# Stub_Tester.net
KiCad netlist of a schematic drawn in Altium Designer
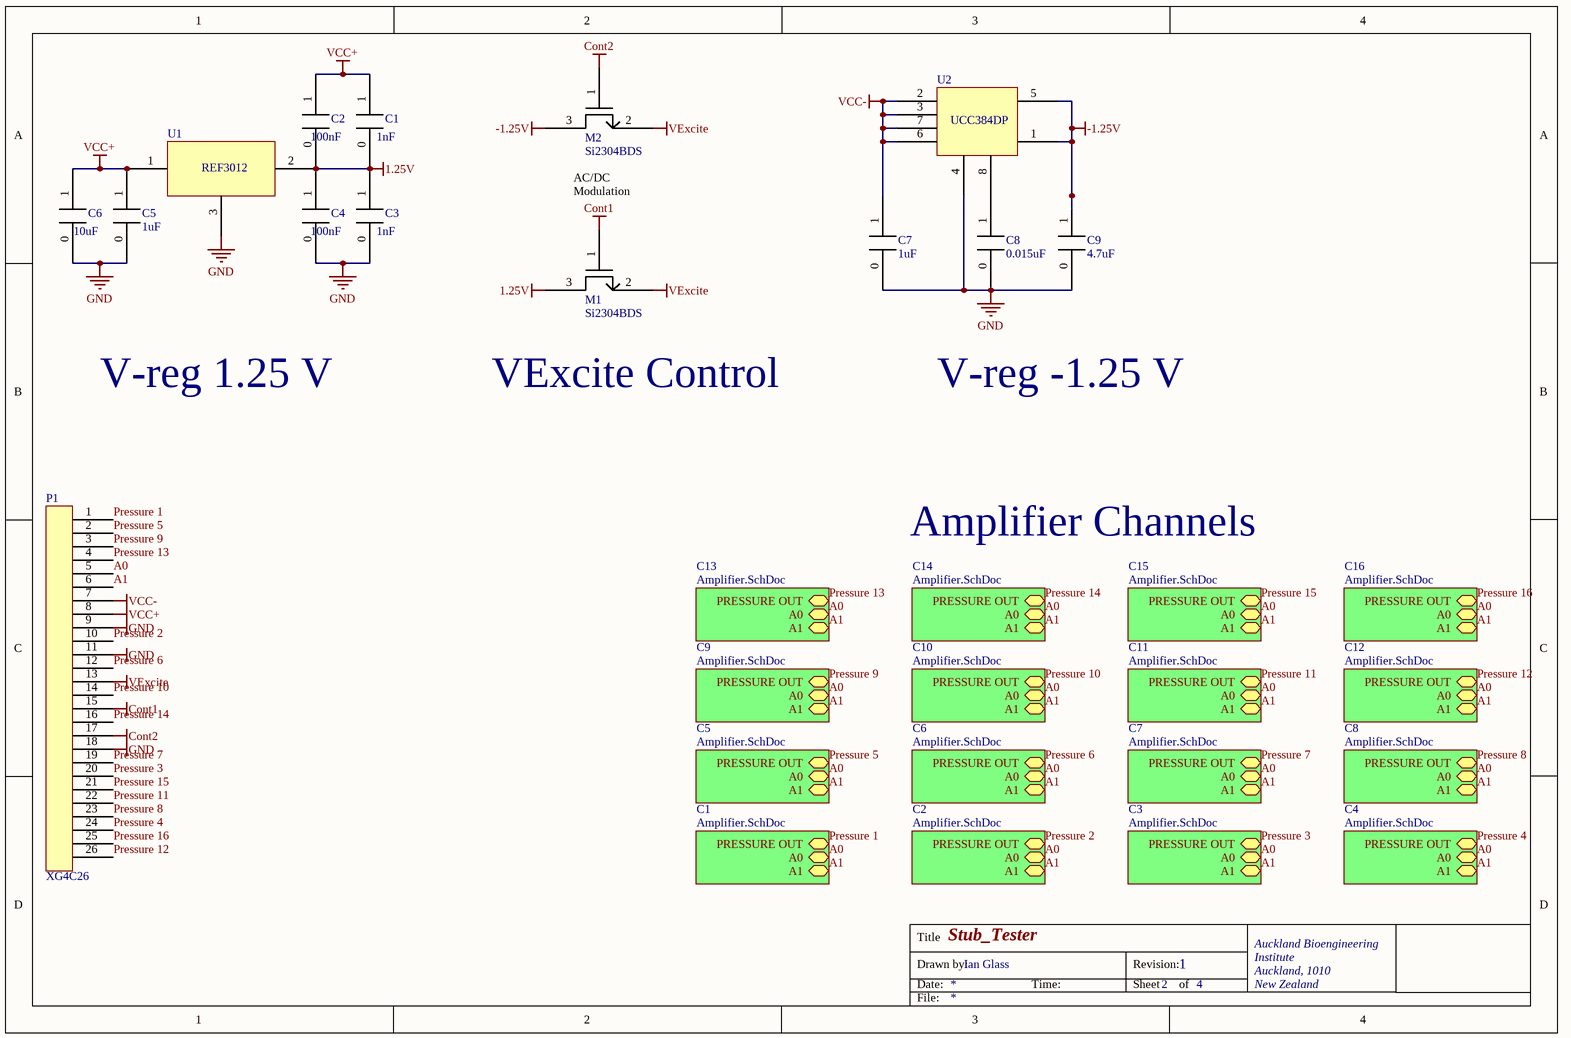
[diagram p0: Stub_Tester.SchDoc]

(export (version "E")
  (design (tool "Eeschema 10.0.6"))
  (components
    (comp (ref "C1")
      (value "1nF")
      (footprint "PcbLib1:C0603 1uF")
      (libsource (lib "Schlib1") (part "C0603 1uF"))
    )
    (comp (ref "C2")
      (value "100nF")
      (footprint "PcbLib1:C0603 1uF")
      (libsource (lib "Schlib1") (part "C0603 1uF"))
    )
    (comp (ref "C3")
      (value "1nF")
      (footprint "PcbLib1:C0603 1uF")
      (libsource (lib "Schlib1") (part "C0603 1uF"))
    )
    (comp (ref "C4")
      (value "100nF")
      (footprint "PcbLib1:C0603 1uF")
      (libsource (lib "Schlib1") (part "C0603 1uF"))
    )
    (comp (ref "C5")
      (value "1uF")
      (footprint "PcbLib1:C0603 1uF")
      (libsource (lib "Schlib1") (part "C0603 1uF"))
    )
    (comp (ref "C6")
      (value "10uF")
      (footprint "PcbLib1:C0603 1uF")
      (libsource (lib "Schlib1") (part "C0603 1uF"))
    )
    (comp (ref "C7")
      (value "1uF")
      (footprint "PcbLib1:C0603 1uF")
      (libsource (lib "Schlib1") (part "C0603 1uF"))
    )
    (comp (ref "C8")
      (value "0.015uF")
      (footprint "PcbLib1:C0603 1uF")
      (libsource (lib "Schlib1") (part "C0603 1uF"))
    )
    (comp (ref "C9")
      (value "4.7uF")
      (footprint "PcbLib1:C0603 1uF")
      (libsource (lib "Schlib1") (part "C0603 1uF"))
    )
    (comp (ref "M1")
      (value "Si2304BDS")
      (footprint "PcbLib1:Si2304BDS")
      (libsource (lib "Schlib1") (part "Si2304BDS"))
    )
    (comp (ref "M2")
      (value "Si2304BDS")
      (footprint "PcbLib1:Si2304BDS")
      (libsource (lib "Schlib1") (part "Si2304BDS"))
    )
    (comp (ref "P1")
      (value "XG4C26")
      (footprint "PcbLib1:XG4C26")
      (libsource (lib "Schlib1") (part "XG4C26"))
    )
    (comp (ref "U1")
      (value "REF3012")
      (footprint "PcbLib1:REF3012")
      (libsource (lib "Schlib1") (part "REF3012"))
    )
    (comp (ref "U2")
      (value "UCC384DP")
      (footprint "PcbLib1:UCC384DP")
      (libsource (lib "Schlib1") (part "UCC384DP"))
    )
  )
  (nets
    (net (code "1") (name "-1.25V") (class "Default")
      (node (ref "C9") (pin "1") (pinfunction "1_1") (pintype "passive"))
      (node (ref "M2") (pin "3") (pinfunction "3_3") (pintype "passive"))
      (node (ref "U2") (pin "1") (pinfunction "1_1") (pintype "passive"))
      (node (ref "U2") (pin "5") (pinfunction "5_5") (pintype "passive"))
    )
    (net (code "2") (name "/A0") (class "Default")
      (node (ref "P1") (pin "5") (pinfunction "5_5") (pintype "passive"))
    )
    (net (code "3") (name "/A1") (class "Default")
      (node (ref "P1") (pin "6") (pinfunction "6_6") (pintype "passive"))
    )
    (net (code "4") (name "/Pressure 1") (class "Default")
      (node (ref "P1") (pin "1") (pinfunction "1_1") (pintype "passive"))
    )
    (net (code "5") (name "/Pressure 2") (class "Default")
      (node (ref "P1") (pin "10") (pinfunction "10_10") (pintype "passive"))
    )
    (net (code "6") (name "/Pressure 3") (class "Default")
      (node (ref "P1") (pin "20") (pinfunction "20_20") (pintype "passive"))
    )
    (net (code "7") (name "/Pressure 4") (class "Default")
      (node (ref "P1") (pin "24") (pinfunction "24_24") (pintype "passive"))
    )
    (net (code "8") (name "/Pressure 5") (class "Default")
      (node (ref "P1") (pin "2") (pinfunction "2_2") (pintype "passive"))
    )
    (net (code "9") (name "/Pressure 6") (class "Default")
      (node (ref "P1") (pin "12") (pinfunction "12_12") (pintype "passive"))
    )
    (net (code "10") (name "/Pressure 7") (class "Default")
      (node (ref "P1") (pin "19") (pinfunction "19_19") (pintype "passive"))
    )
    (net (code "11") (name "/Pressure 8") (class "Default")
      (node (ref "P1") (pin "23") (pinfunction "23_23") (pintype "passive"))
    )
    (net (code "12") (name "/Pressure 9") (class "Default")
      (node (ref "P1") (pin "3") (pinfunction "3_3") (pintype "passive"))
    )
    (net (code "13") (name "/Pressure 10") (class "Default")
      (node (ref "P1") (pin "14") (pinfunction "14_14") (pintype "passive"))
    )
    (net (code "14") (name "/Pressure 11") (class "Default")
      (node (ref "P1") (pin "22") (pinfunction "22_22") (pintype "passive"))
    )
    (net (code "15") (name "/Pressure 12") (class "Default")
      (node (ref "P1") (pin "26") (pinfunction "26_26") (pintype "passive"))
    )
    (net (code "16") (name "/Pressure 13") (class "Default")
      (node (ref "P1") (pin "4") (pinfunction "4_4") (pintype "passive"))
    )
    (net (code "17") (name "/Pressure 14") (class "Default")
      (node (ref "P1") (pin "16") (pinfunction "16_16") (pintype "passive"))
    )
    (net (code "18") (name "/Pressure 15") (class "Default")
      (node (ref "P1") (pin "21") (pinfunction "21_21") (pintype "passive"))
    )
    (net (code "19") (name "/Pressure 16") (class "Default")
      (node (ref "P1") (pin "25") (pinfunction "25_25") (pintype "passive"))
    )
    (net (code "20") (name "1.25V") (class "Default")
      (node (ref "C1") (pin "0") (pinfunction "0_0") (pintype "passive"))
      (node (ref "C2") (pin "0") (pinfunction "0_0") (pintype "passive"))
      (node (ref "C3") (pin "1") (pinfunction "1_1") (pintype "passive"))
      (node (ref "C4") (pin "1") (pinfunction "1_1") (pintype "passive"))
      (node (ref "M1") (pin "3") (pinfunction "3_3") (pintype "passive"))
      (node (ref "U1") (pin "2") (pinfunction "2_2") (pintype "passive"))
    )
    (net (code "21") (name "Cont1") (class "Default")
      (node (ref "M1") (pin "1") (pinfunction "1_1") (pintype "passive"))
      (node (ref "P1") (pin "15") (pinfunction "15_15") (pintype "passive"))
    )
    (net (code "22") (name "Cont2") (class "Default")
      (node (ref "M2") (pin "1") (pinfunction "1_1") (pintype "passive"))
      (node (ref "P1") (pin "17") (pinfunction "17_17") (pintype "passive"))
    )
    (net (code "23") (name "GND") (class "Default")
      (node (ref "C3") (pin "0") (pinfunction "0_0") (pintype "passive"))
      (node (ref "C4") (pin "0") (pinfunction "0_0") (pintype "passive"))
      (node (ref "C5") (pin "0") (pinfunction "0_0") (pintype "passive"))
      (node (ref "C6") (pin "0") (pinfunction "0_0") (pintype "passive"))
      (node (ref "C7") (pin "0") (pinfunction "0_0") (pintype "passive"))
      (node (ref "C8") (pin "0") (pinfunction "0_0") (pintype "passive"))
      (node (ref "C9") (pin "0") (pinfunction "0_0") (pintype "passive"))
      (node (ref "P1") (pin "11") (pinfunction "11_11") (pintype "passive"))
      (node (ref "P1") (pin "18") (pinfunction "18_18") (pintype "passive"))
      (node (ref "P1") (pin "9") (pinfunction "9_9") (pintype "passive"))
      (node (ref "U1") (pin "3") (pinfunction "3_3") (pintype "passive"))
      (node (ref "U2") (pin "4") (pinfunction "4_4") (pintype "passive"))
    )
    (net (code "24") (name "Net-(C8-Pad1)") (class "Default")
      (node (ref "C8") (pin "1") (pinfunction "1_1") (pintype "passive"))
      (node (ref "U2") (pin "8") (pinfunction "8_8") (pintype "passive"))
    )
    (net (code "25") (name "VCC+") (class "Default")
      (node (ref "C1") (pin "1") (pinfunction "1_1") (pintype "passive"))
      (node (ref "C2") (pin "1") (pinfunction "1_1") (pintype "passive"))
      (node (ref "C5") (pin "1") (pinfunction "1_1") (pintype "passive"))
      (node (ref "C6") (pin "1") (pinfunction "1_1") (pintype "passive"))
      (node (ref "P1") (pin "8") (pinfunction "8_8") (pintype "passive"))
      (node (ref "U1") (pin "1") (pinfunction "1_1") (pintype "passive"))
    )
    (net (code "26") (name "VCC-") (class "Default")
      (node (ref "C7") (pin "1") (pinfunction "1_1") (pintype "passive"))
      (node (ref "P1") (pin "7") (pinfunction "7_7") (pintype "passive"))
      (node (ref "U2") (pin "2") (pinfunction "2_2") (pintype "passive"))
      (node (ref "U2") (pin "3") (pinfunction "3_3") (pintype "passive"))
      (node (ref "U2") (pin "6") (pinfunction "6_6") (pintype "passive"))
      (node (ref "U2") (pin "7") (pinfunction "7_7") (pintype "passive"))
    )
    (net (code "27") (name "VExcite") (class "Default")
      (node (ref "M1") (pin "2") (pinfunction "2_2") (pintype "passive"))
      (node (ref "M2") (pin "2") (pinfunction "2_2") (pintype "passive"))
      (node (ref "P1") (pin "13") (pinfunction "13_13") (pintype "passive"))
    )
  )
)
